# AmpSSM2019_230307.net
KiCad netlist of a schematic drawn in EAGLE
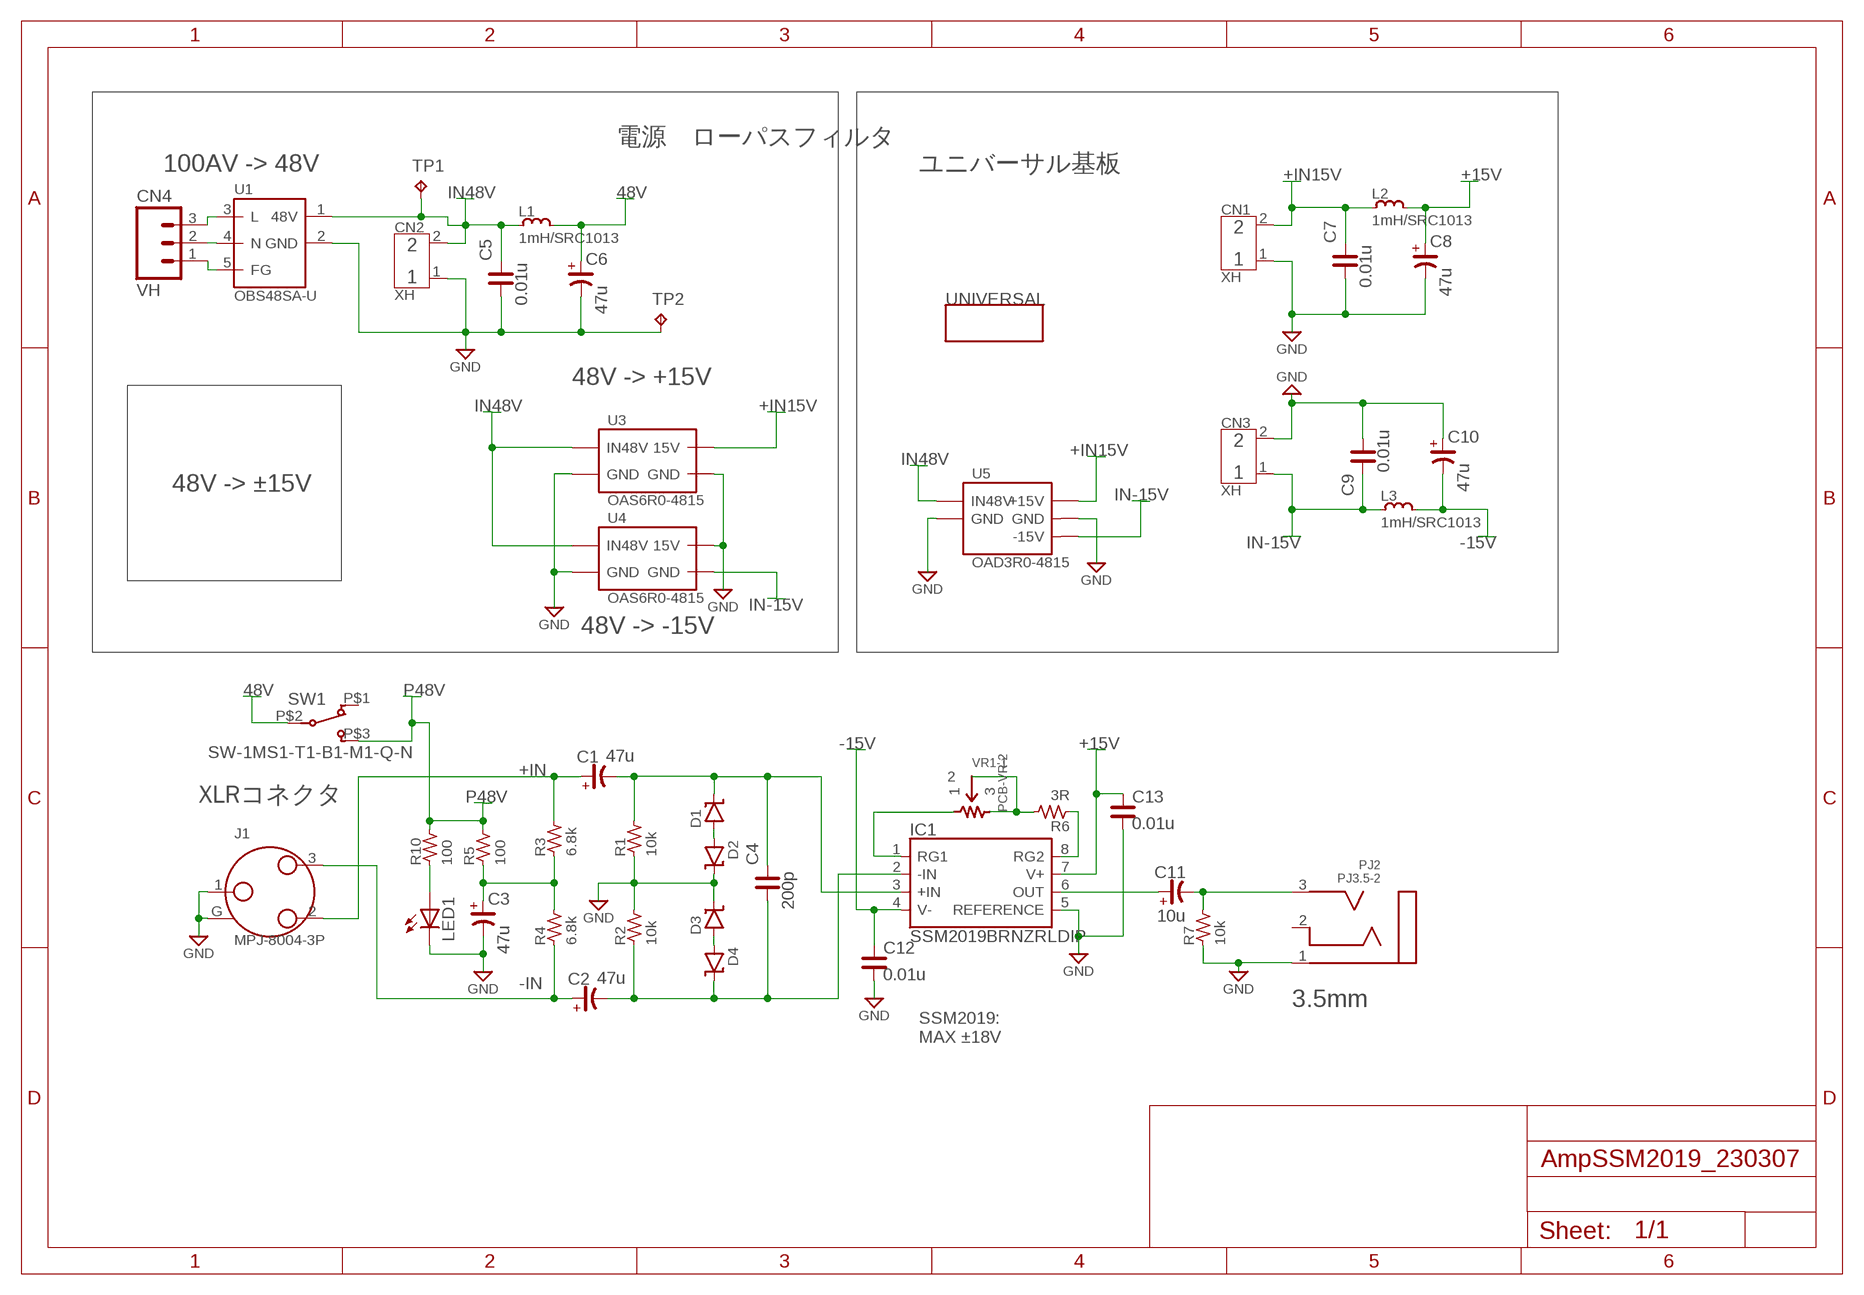
[diagram p0: schematic, sheet 1]

(export (version "E")
  (design (tool "Eeschema 10.0.6"))
  (components
    (comp (ref "C1")
      (value "47u")
      (footprint "eagle-import:CE-025X065")
      (libsource (lib "eagle-import") (part "CP_C025X065"))
    )
    (comp (ref "C2")
      (value "47u")
      (footprint "eagle-import:CE-025X065")
      (libsource (lib "eagle-import") (part "CP_C025X065"))
    )
    (comp (ref "C3")
      (value "47u")
      (footprint "eagle-import:CE-025X065")
      (libsource (lib "eagle-import") (part "CP_C025X065"))
    )
    (comp (ref "C4")
      (value "200p")
      (footprint "eagle-import:C0603")
      (libsource (lib "eagle-import") (part "C_0603"))
    )
    (comp (ref "C5")
      (value "0.01u")
      (footprint "eagle-import:C0603")
      (libsource (lib "eagle-import") (part "C_0603"))
    )
    (comp (ref "C6")
      (value "47u")
      (footprint "eagle-import:CE-025X065")
      (libsource (lib "eagle-import") (part "CP_C025X065"))
    )
    (comp (ref "C7")
      (value "0.01u")
      (footprint "eagle-import:C0603")
      (libsource (lib "eagle-import") (part "C_0603"))
    )
    (comp (ref "C8")
      (value "47u")
      (footprint "eagle-import:CE-025X065")
      (libsource (lib "eagle-import") (part "CP_C025X065"))
    )
    (comp (ref "C9")
      (value "0.01u")
      (footprint "eagle-import:C0603")
      (libsource (lib "eagle-import") (part "C_0603"))
    )
    (comp (ref "C10")
      (value "47u")
      (footprint "eagle-import:CE-025X065")
      (libsource (lib "eagle-import") (part "CP_C025X065"))
    )
    (comp (ref "C11")
      (value "10u")
      (footprint "eagle-import:CE-025X065")
      (libsource (lib "eagle-import") (part "CP_C025X065"))
    )
    (comp (ref "C12")
      (value "0.01u")
      (footprint "eagle-import:C0603")
      (libsource (lib "eagle-import") (part "C_0603"))
    )
    (comp (ref "C13")
      (value "0.01u")
      (footprint "eagle-import:C0603")
      (libsource (lib "eagle-import") (part "C_0603"))
    )
    (comp (ref "CN1")
      (value "XH")
      (footprint "eagle-import:B2B-XH-A")
      (libsource (lib "eagle-import") (part "CN-B2B-XH-A"))
    )
    (comp (ref "CN2")
      (value "XH")
      (footprint "eagle-import:B2B-XH-A")
      (libsource (lib "eagle-import") (part "CN-B2B-XH-A"))
    )
    (comp (ref "CN3")
      (value "XH")
      (footprint "eagle-import:B2B-XH-A")
      (libsource (lib "eagle-import") (part "CN-B2B-XH-A"))
    )
    (comp (ref "CN4")
      (value "VH")
      (footprint "eagle-import:VH3")
      (libsource (lib "eagle-import") (part "M03VH"))
    )
    (comp (ref "D1")
      (value "ZD323")
      (footprint "eagle-import:SOD-323")
      (libsource (lib "eagle-import") (part "ZD323"))
    )
    (comp (ref "D2")
      (value "ZD323")
      (footprint "eagle-import:SOD-323")
      (libsource (lib "eagle-import") (part "ZD323"))
    )
    (comp (ref "D3")
      (value "ZD323")
      (footprint "eagle-import:SOD-323")
      (libsource (lib "eagle-import") (part "ZD323"))
    )
    (comp (ref "D4")
      (value "ZD323")
      (footprint "eagle-import:SOD-323")
      (libsource (lib "eagle-import") (part "ZD323"))
    )
    (comp (ref "IC1")
      (value "SSM2019BRNZRLDIP")
      (footprint "eagle-import:DIL08")
      (libsource (lib "eagle-import") (part "SSM2019BRNZRLDIP"))
    )
    (comp (ref "J1")
      (value "MPJ-8004-3P")
      (footprint "eagle-import:MPJ-8004-3P")
      (libsource (lib "eagle-import") (part "MPJ-8004-3P"))
    )
    (comp (ref "L1")
      (value "1mH/SRC1013")
      (footprint "eagle-import:L13X15")
      (libsource (lib "eagle-import") (part "L_13X15"))
    )
    (comp (ref "L2")
      (value "1mH/SRC1013")
      (footprint "eagle-import:L13X15")
      (libsource (lib "eagle-import") (part "L_13X15"))
    )
    (comp (ref "L3")
      (value "1mH/SRC1013")
      (footprint "eagle-import:L13X15")
      (libsource (lib "eagle-import") (part "L_13X15"))
    )
    (comp (ref "LED1")
      (value "LED3MM")
      (footprint "eagle-import:LED3MM")
      (libsource (lib "eagle-import") (part "LED3MM"))
    )
    (comp (ref "PJ2")
      (value "PJ3.5-2")
      (footprint "eagle-import:PJ3.5-2")
      (libsource (lib "eagle-import") (part "PJ3.5-2"))
    )
    (comp (ref "R1")
      (value "10k")
      (footprint "eagle-import:R0603")
      (libsource (lib "eagle-import") (part "R_0603"))
    )
    (comp (ref "R2")
      (value "10k")
      (footprint "eagle-import:R0603")
      (libsource (lib "eagle-import") (part "R_0603"))
    )
    (comp (ref "R3")
      (value "6.8k")
      (footprint "eagle-import:R0603")
      (libsource (lib "eagle-import") (part "R_0603"))
    )
    (comp (ref "R4")
      (value "6.8k")
      (footprint "eagle-import:R0603")
      (libsource (lib "eagle-import") (part "R_0603"))
    )
    (comp (ref "R5")
      (value "100")
      (footprint "eagle-import:R0603")
      (libsource (lib "eagle-import") (part "R_0603"))
    )
    (comp (ref "R6")
      (value "3R")
      (footprint "eagle-import:R0603")
      (libsource (lib "eagle-import") (part "R_0603"))
    )
    (comp (ref "R7")
      (value "10k")
      (footprint "eagle-import:R0603")
      (libsource (lib "eagle-import") (part "R_0603"))
    )
    (comp (ref "R10")
      (value "100")
      (footprint "eagle-import:R0603")
      (libsource (lib "eagle-import") (part "R_0603"))
    )
    (comp (ref "SW1")
      (value "SW-1MS1-T1-B1-M1-Q-N")
      (footprint "eagle-import:1MS1-T1-B1-M1-Q-N")
      (libsource (lib "eagle-import") (part "SW-1MS1-T1-B1-M1-Q-N"))
    )
    (comp (ref "TP1")
      (value "TPPAD1-13")
      (footprint "eagle-import:P1-13")
      (libsource (lib "eagle-import") (part "TPPAD1-13"))
    )
    (comp (ref "TP2")
      (value "TPPAD1-13")
      (footprint "eagle-import:P1-13")
      (libsource (lib "eagle-import") (part "TPPAD1-13"))
    )
    (comp (ref "U1")
      (value "OBS48SA-U")
      (footprint "eagle-import:OBS48SA-U")
      (libsource (lib "eagle-import") (part "OBS48SA-U"))
    )
    (comp (ref "U2")
      (value "UNIVERSAL10X10")
      (footprint "eagle-import:UNIVERSAL10X10")
      (libsource (lib "eagle-import") (part "UNIVERSAL10X10"))
    )
    (comp (ref "U3")
      (value "OAS6R0-4815")
      (footprint "eagle-import:OAS6R0-4815")
      (libsource (lib "eagle-import") (part "OAS6R0-4815"))
    )
    (comp (ref "U4")
      (value "OAS6R0-4815")
      (footprint "eagle-import:OAS6R0-4815")
      (libsource (lib "eagle-import") (part "OAS6R0-4815"))
    )
    (comp (ref "U5")
      (value "OAD3R0-4815")
      (footprint "eagle-import:OAD3R0-4815")
      (libsource (lib "eagle-import") (part "OAD3R0-4815"))
    )
    (comp (ref "VR1")
      (value "PCB-VR-2")
      (footprint "eagle-import:PCB-VR-2")
      (libsource (lib "eagle-import") (part "PCB-VR-2"))
    )
  )
  (nets
    (net (code "1") (name "/+15V") (class "Default")
      (node (ref "C13") (pin "2") (pinfunction "2_2") (pintype "passive"))
      (node (ref "C8") (pin "+") (pinfunction "+_+") (pintype "passive"))
      (node (ref "IC1") (pin "7") (pinfunction "V+_7") (pintype "bidirectional"))
      (node (ref "L2") (pin "2") (pinfunction "2_2") (pintype "passive"))
    )
    (net (code "2") (name "/+IN") (class "Default")
      (node (ref "C1") (pin "+") (pinfunction "+_+") (pintype "passive"))
      (node (ref "J1") (pin "2") (pinfunction "2_2") (pintype "bidirectional"))
      (node (ref "R3") (pin "2") (pinfunction "2_2") (pintype "passive"))
    )
    (net (code "3") (name "/+IN15V") (class "Default")
      (node (ref "C7") (pin "2") (pinfunction "2_2") (pintype "passive"))
      (node (ref "CN1") (pin "2") (pinfunction "2_2") (pintype "passive"))
      (node (ref "L2") (pin "1") (pinfunction "1_1") (pintype "passive"))
      (node (ref "U3") (pin "V_OUT") (pinfunction "15V_V_OUT") (pintype "bidirectional"))
      (node (ref "U5") (pin "V+_OUT") (pinfunction "+15V_V+_OUT") (pintype "bidirectional"))
    )
    (net (code "4") (name "/-15V") (class "Default")
      (node (ref "C10") (pin "-") (pinfunction "-_-") (pintype "passive"))
      (node (ref "C12") (pin "2") (pinfunction "2_2") (pintype "passive"))
      (node (ref "IC1") (pin "4") (pinfunction "V-_4") (pintype "bidirectional"))
      (node (ref "L3") (pin "2") (pinfunction "2_2") (pintype "passive"))
    )
    (net (code "5") (name "/-IN") (class "Default")
      (node (ref "C2") (pin "+") (pinfunction "+_+") (pintype "passive"))
      (node (ref "J1") (pin "3") (pinfunction "3_3") (pintype "bidirectional"))
      (node (ref "R4") (pin "1") (pinfunction "1_1") (pintype "passive"))
    )
    (net (code "6") (name "/48V") (class "Default")
      (node (ref "C6") (pin "+") (pinfunction "+_+") (pintype "passive"))
      (node (ref "L1") (pin "2") (pinfunction "2_2") (pintype "passive"))
      (node (ref "SW1") (pin "P$2") (pinfunction "P_P$2") (pintype "passive"))
    )
    (net (code "7") (name "/IN-15V") (class "Default")
      (node (ref "C9") (pin "2") (pinfunction "2_2") (pintype "passive"))
      (node (ref "CN3") (pin "1") (pinfunction "1_1") (pintype "passive"))
      (node (ref "L3") (pin "1") (pinfunction "1_1") (pintype "passive"))
      (node (ref "U4") (pin "G_OUT") (pinfunction "GND_G_OUT") (pintype "bidirectional"))
      (node (ref "U5") (pin "V-_OUT") (pinfunction "-15V_V-_OUT") (pintype "bidirectional"))
    )
    (net (code "8") (name "/IN48V") (class "Default")
      (node (ref "C5") (pin "2") (pinfunction "2_2") (pintype "passive"))
      (node (ref "CN2") (pin "2") (pinfunction "2_2") (pintype "passive"))
      (node (ref "L1") (pin "1") (pinfunction "1_1") (pintype "passive"))
      (node (ref "TP1") (pin "TP") (pinfunction "TP_TP") (pintype "input"))
      (node (ref "U1") (pin "1") (pinfunction "48V_1") (pintype "bidirectional"))
      (node (ref "U3") (pin "VIN") (pinfunction "IN48V_VIN") (pintype "bidirectional"))
      (node (ref "U4") (pin "VIN") (pinfunction "IN48V_VIN") (pintype "bidirectional"))
      (node (ref "U5") (pin "VIN") (pinfunction "IN48V_VIN") (pintype "bidirectional"))
    )
    (net (code "9") (name "/P48V") (class "Default")
      (node (ref "R10") (pin "2") (pinfunction "2_2") (pintype "passive"))
      (node (ref "R5") (pin "2") (pinfunction "2_2") (pintype "passive"))
      (node (ref "SW1") (pin "P$3") (pinfunction "S_P$3") (pintype "passive"))
    )
    (net (code "10") (name "G") (class "Default")
      (node (ref "C10") (pin "+") (pinfunction "+_+") (pintype "passive"))
      (node (ref "C12") (pin "1") (pinfunction "1_1") (pintype "passive"))
      (node (ref "C13") (pin "1") (pinfunction "1_1") (pintype "passive"))
      (node (ref "C3") (pin "-") (pinfunction "-_-") (pintype "passive"))
      (node (ref "C5") (pin "1") (pinfunction "1_1") (pintype "passive"))
      (node (ref "C6") (pin "-") (pinfunction "-_-") (pintype "passive"))
      (node (ref "C7") (pin "1") (pinfunction "1_1") (pintype "passive"))
      (node (ref "C8") (pin "-") (pinfunction "-_-") (pintype "passive"))
      (node (ref "C9") (pin "1") (pinfunction "1_1") (pintype "passive"))
      (node (ref "CN1") (pin "1") (pinfunction "1_1") (pintype "passive"))
      (node (ref "CN2") (pin "1") (pinfunction "1_1") (pintype "passive"))
      (node (ref "CN3") (pin "2") (pinfunction "2_2") (pintype "passive"))
      (node (ref "D2") (pin "K") (pinfunction "C_K") (pintype "passive"))
      (node (ref "D3") (pin "K") (pinfunction "C_K") (pintype "passive"))
      (node (ref "IC1") (pin "5") (pinfunction "REFERENCE_5") (pintype "bidirectional"))
      (node (ref "J1") (pin "1") (pinfunction "1_1") (pintype "bidirectional"))
      (node (ref "J1") (pin "G") (pinfunction "G_G") (pintype "bidirectional"))
      (node (ref "LED1") (pin "K") (pinfunction "C_K") (pintype "passive"))
      (node (ref "PJ2") (pin "1") (pinfunction "S_1") (pintype "passive"))
      (node (ref "R1") (pin "1") (pinfunction "1_1") (pintype "passive"))
      (node (ref "R2") (pin "2") (pinfunction "2_2") (pintype "passive"))
      (node (ref "R7") (pin "1") (pinfunction "1_1") (pintype "passive"))
      (node (ref "TP2") (pin "TP") (pinfunction "TP_TP") (pintype "input"))
      (node (ref "U1") (pin "2") (pinfunction "GND_2") (pintype "bidirectional"))
      (node (ref "U3") (pin "G_IN") (pinfunction "GND_G_IN") (pintype "bidirectional"))
      (node (ref "U3") (pin "G_OUT") (pinfunction "GND_G_OUT") (pintype "bidirectional"))
      (node (ref "U4") (pin "G_IN") (pinfunction "GND_G_IN") (pintype "bidirectional"))
      (node (ref "U4") (pin "V_OUT") (pinfunction "15V_V_OUT") (pintype "bidirectional"))
      (node (ref "U5") (pin "G_IN") (pinfunction "GND_G_IN") (pintype "bidirectional"))
      (node (ref "U5") (pin "G_OUT") (pinfunction "GND_G_OUT") (pintype "bidirectional"))
    )
    (net (code "11") (name "Net-(C3-Pad+)") (class "Default")
      (node (ref "C3") (pin "+") (pinfunction "+_+") (pintype "passive"))
      (node (ref "R3") (pin "1") (pinfunction "1_1") (pintype "passive"))
      (node (ref "R4") (pin "2") (pinfunction "2_2") (pintype "passive"))
      (node (ref "R5") (pin "1") (pinfunction "1_1") (pintype "passive"))
    )
    (net (code "12") (name "Net-(D1-C)") (class "Default")
      (node (ref "C1") (pin "-") (pinfunction "-_-") (pintype "passive"))
      (node (ref "C4") (pin "2") (pinfunction "2_2") (pintype "passive"))
      (node (ref "D1") (pin "K") (pinfunction "C_K") (pintype "passive"))
      (node (ref "IC1") (pin "3") (pinfunction "+IN_3") (pintype "bidirectional"))
      (node (ref "R1") (pin "2") (pinfunction "2_2") (pintype "passive"))
    )
    (net (code "13") (name "Net-(D1-PadA)") (class "Default")
      (node (ref "D1") (pin "A") (pinfunction "A_A") (pintype "passive"))
      (node (ref "D2") (pin "A") (pinfunction "A_A") (pintype "passive"))
    )
    (net (code "14") (name "Net-(D3-PadA)") (class "Default")
      (node (ref "D3") (pin "A") (pinfunction "A_A") (pintype "passive"))
      (node (ref "D4") (pin "A") (pinfunction "A_A") (pintype "passive"))
    )
    (net (code "15") (name "Net-(D4-C)") (class "Default")
      (node (ref "C2") (pin "-") (pinfunction "-_-") (pintype "passive"))
      (node (ref "C4") (pin "1") (pinfunction "1_1") (pintype "passive"))
      (node (ref "D4") (pin "K") (pinfunction "C_K") (pintype "passive"))
      (node (ref "IC1") (pin "2") (pinfunction "-IN_2") (pintype "bidirectional"))
      (node (ref "R2") (pin "1") (pinfunction "1_1") (pintype "passive"))
    )
    (net (code "16") (name "Net-(IC1-OUT)") (class "Default")
      (node (ref "C11") (pin "+") (pinfunction "+_+") (pintype "passive"))
      (node (ref "IC1") (pin "6") (pinfunction "OUT_6") (pintype "bidirectional"))
    )
    (net (code "17") (name "Net-(IC1-RG1)") (class "Default")
      (node (ref "IC1") (pin "1") (pinfunction "RG1_1") (pintype "bidirectional"))
      (node (ref "VR1") (pin "3") (pinfunction "1_3") (pintype "passive"))
    )
    (net (code "18") (name "Net-(IC1-RG2)") (class "Default")
      (node (ref "IC1") (pin "8") (pinfunction "RG2_8") (pintype "bidirectional"))
      (node (ref "R6") (pin "1") (pinfunction "1_1") (pintype "passive"))
    )
    (net (code "19") (name "Net-(LED1-PadA)") (class "Default")
      (node (ref "LED1") (pin "A") (pinfunction "A_A") (pintype "passive"))
      (node (ref "R10") (pin "1") (pinfunction "1_1") (pintype "passive"))
    )
    (net (code "20") (name "Net-(PJ2-TIP)") (class "Default")
      (node (ref "C11") (pin "-") (pinfunction "-_-") (pintype "passive"))
      (node (ref "PJ2") (pin "3") (pinfunction "TIP_3") (pintype "passive"))
      (node (ref "R7") (pin "2") (pinfunction "2_2") (pintype "passive"))
    )
    (net (code "21") (name "Net-(U1-FG)") (class "Default")
      (node (ref "CN4") (pin "1") (pinfunction "1_1") (pintype "passive"))
      (node (ref "U1") (pin "5") (pinfunction "FG_5") (pintype "bidirectional"))
    )
    (net (code "22") (name "Net-(U1-L)") (class "Default")
      (node (ref "CN4") (pin "3") (pinfunction "3_3") (pintype "passive"))
      (node (ref "U1") (pin "3") (pinfunction "L_3") (pintype "bidirectional"))
    )
    (net (code "23") (name "Net-(U1-N)") (class "Default")
      (node (ref "CN4") (pin "2") (pinfunction "2_2") (pintype "passive"))
      (node (ref "U1") (pin "4") (pinfunction "N_4") (pintype "bidirectional"))
    )
    (net (code "24") (name "Net-(VR1A-3)") (class "Default")
      (node (ref "R6") (pin "2") (pinfunction "2_2") (pintype "passive"))
      (node (ref "VR1") (pin "1") (pinfunction "3_1") (pintype "passive"))
      (node (ref "VR1") (pin "2") (pinfunction "2_2") (pintype "passive"))
    )
    (net (code "25") (name "unconnected-(PJ2-RING-Pad2)") (class "Default")
      (node (ref "PJ2") (pin "2") (pinfunction "RING_2") (pintype "passive"))
    )
    (net (code "26") (name "unconnected-(SW1-O-PadP$1)") (class "Default")
      (node (ref "SW1") (pin "P$1") (pinfunction "O_P$1") (pintype "passive"))
    )
  )
)
